# M500B.net
KiCad netlist of a schematic drawn in EAGLE
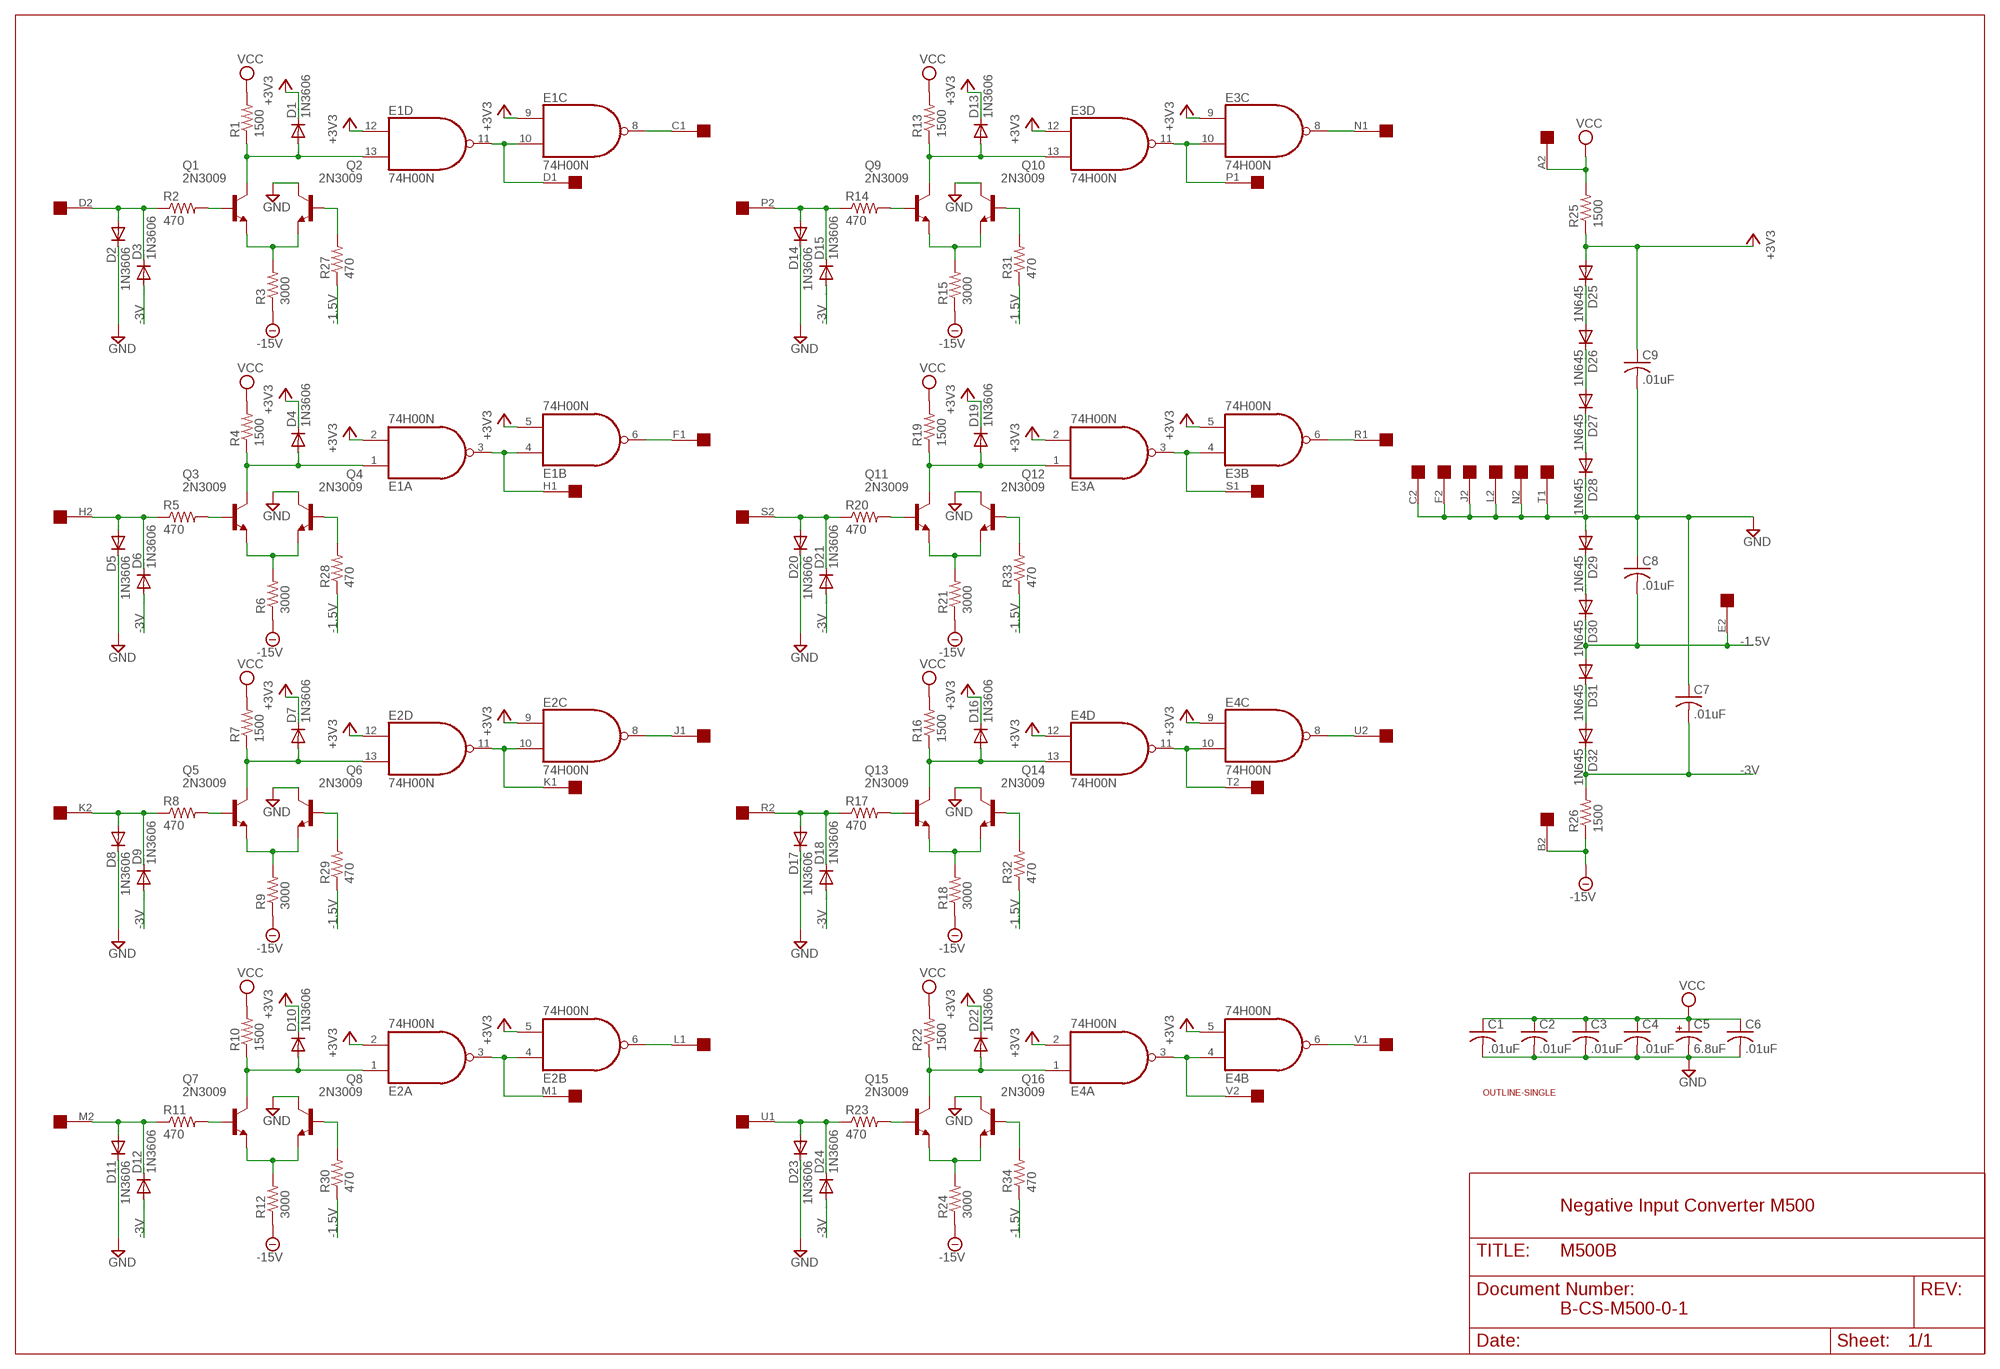
[diagram p0: schematic, sheet 1]

(export (version "E")
  (design (tool "Eeschema 10.0.6"))
  (components
    (comp (ref "C1")
      (value ".01uF")
      (footprint "eagle-import:C050-025X075")
      (libsource (lib "eagle-import") (part "C-US050-025X075"))
    )
    (comp (ref "C2")
      (value ".01uF")
      (footprint "eagle-import:C050-025X075")
      (libsource (lib "eagle-import") (part "C-US050-025X075"))
    )
    (comp (ref "C3")
      (value ".01uF")
      (footprint "eagle-import:C050-025X075")
      (libsource (lib "eagle-import") (part "C-US050-025X075"))
    )
    (comp (ref "C4")
      (value ".01uF")
      (footprint "eagle-import:C050-025X075")
      (libsource (lib "eagle-import") (part "C-US050-025X075"))
    )
    (comp (ref "C5")
      (value "6.8uF")
      (footprint "eagle-import:E12-8")
      (libsource (lib "eagle-import") (part "CPOL-USE20-8AXIAL"))
    )
    (comp (ref "C6")
      (value ".01uF")
      (footprint "eagle-import:C050-025X075")
      (libsource (lib "eagle-import") (part "C-US050-025X075"))
    )
    (comp (ref "C7")
      (value ".01uF")
      (footprint "eagle-import:C050-025X075")
      (libsource (lib "eagle-import") (part "C-US050-025X075"))
    )
    (comp (ref "C8")
      (value ".01uF")
      (footprint "eagle-import:C050-025X075")
      (libsource (lib "eagle-import") (part "C-US050-025X075"))
    )
    (comp (ref "C9")
      (value ".01uF")
      (footprint "eagle-import:C050-025X075")
      (libsource (lib "eagle-import") (part "C-US050-025X075"))
    )
    (comp (ref "D1")
      (value "1N3606")
      (footprint "eagle-import:DO35-10")
      (libsource (lib "eagle-import") (part "1N4148DO35-10"))
    )
    (comp (ref "D2")
      (value "1N3606")
      (footprint "eagle-import:DO35-10")
      (libsource (lib "eagle-import") (part "1N4148DO35-10"))
    )
    (comp (ref "D3")
      (value "1N3606")
      (footprint "eagle-import:DO35-10")
      (libsource (lib "eagle-import") (part "1N4148DO35-10"))
    )
    (comp (ref "D4")
      (value "1N3606")
      (footprint "eagle-import:DO35-10")
      (libsource (lib "eagle-import") (part "1N4148DO35-10"))
    )
    (comp (ref "D5")
      (value "1N3606")
      (footprint "eagle-import:DO35-10")
      (libsource (lib "eagle-import") (part "1N4148DO35-10"))
    )
    (comp (ref "D6")
      (value "1N3606")
      (footprint "eagle-import:DO35-10")
      (libsource (lib "eagle-import") (part "1N4148DO35-10"))
    )
    (comp (ref "D7")
      (value "1N3606")
      (footprint "eagle-import:DO35-10")
      (libsource (lib "eagle-import") (part "1N4148DO35-10"))
    )
    (comp (ref "D8")
      (value "1N3606")
      (footprint "eagle-import:DO35-10")
      (libsource (lib "eagle-import") (part "1N4148DO35-10"))
    )
    (comp (ref "D9")
      (value "1N3606")
      (footprint "eagle-import:DO35-10")
      (libsource (lib "eagle-import") (part "1N4148DO35-10"))
    )
    (comp (ref "D10")
      (value "1N3606")
      (footprint "eagle-import:DO35-10")
      (libsource (lib "eagle-import") (part "1N4148DO35-10"))
    )
    (comp (ref "D11")
      (value "1N3606")
      (footprint "eagle-import:DO35-10")
      (libsource (lib "eagle-import") (part "1N4148DO35-10"))
    )
    (comp (ref "D12")
      (value "1N3606")
      (footprint "eagle-import:DO35-10")
      (libsource (lib "eagle-import") (part "1N4148DO35-10"))
    )
    (comp (ref "D13")
      (value "1N3606")
      (footprint "eagle-import:DO35-10")
      (libsource (lib "eagle-import") (part "1N4148DO35-10"))
    )
    (comp (ref "D14")
      (value "1N3606")
      (footprint "eagle-import:DO35-10")
      (libsource (lib "eagle-import") (part "1N4148DO35-10"))
    )
    (comp (ref "D15")
      (value "1N3606")
      (footprint "eagle-import:DO35-10")
      (libsource (lib "eagle-import") (part "1N4148DO35-10"))
    )
    (comp (ref "D16")
      (value "1N3606")
      (footprint "eagle-import:DO35-10")
      (libsource (lib "eagle-import") (part "1N4148DO35-10"))
    )
    (comp (ref "D17")
      (value "1N3606")
      (footprint "eagle-import:DO35-10")
      (libsource (lib "eagle-import") (part "1N4148DO35-10"))
    )
    (comp (ref "D18")
      (value "1N3606")
      (footprint "eagle-import:DO35-10")
      (libsource (lib "eagle-import") (part "1N4148DO35-10"))
    )
    (comp (ref "D19")
      (value "1N3606")
      (footprint "eagle-import:DO35-10")
      (libsource (lib "eagle-import") (part "1N4148DO35-10"))
    )
    (comp (ref "D20")
      (value "1N3606")
      (footprint "eagle-import:DO35-10")
      (libsource (lib "eagle-import") (part "1N4148DO35-10"))
    )
    (comp (ref "D21")
      (value "1N3606")
      (footprint "eagle-import:DO35-10")
      (libsource (lib "eagle-import") (part "1N4148DO35-10"))
    )
    (comp (ref "D22")
      (value "1N3606")
      (footprint "eagle-import:DO35-10")
      (libsource (lib "eagle-import") (part "1N4148DO35-10"))
    )
    (comp (ref "D23")
      (value "1N3606")
      (footprint "eagle-import:DO35-10")
      (libsource (lib "eagle-import") (part "1N4148DO35-10"))
    )
    (comp (ref "D24")
      (value "1N3606")
      (footprint "eagle-import:DO35-10")
      (libsource (lib "eagle-import") (part "1N4148DO35-10"))
    )
    (comp (ref "D25")
      (value "1N645")
      (footprint "eagle-import:DO35-10")
      (libsource (lib "eagle-import") (part "1N4148DO35-10"))
    )
    (comp (ref "D26")
      (value "1N645")
      (footprint "eagle-import:DO35-10")
      (libsource (lib "eagle-import") (part "1N4148DO35-10"))
    )
    (comp (ref "D27")
      (value "1N645")
      (footprint "eagle-import:DO35-10")
      (libsource (lib "eagle-import") (part "1N4148DO35-10"))
    )
    (comp (ref "D28")
      (value "1N645")
      (footprint "eagle-import:DO35-10")
      (libsource (lib "eagle-import") (part "1N4148DO35-10"))
    )
    (comp (ref "D29")
      (value "1N645")
      (footprint "eagle-import:DO35-10")
      (libsource (lib "eagle-import") (part "1N4148DO35-10"))
    )
    (comp (ref "D30")
      (value "1N645")
      (footprint "eagle-import:DO35-10")
      (libsource (lib "eagle-import") (part "1N4148DO35-10"))
    )
    (comp (ref "D31")
      (value "1N645")
      (footprint "eagle-import:DO35-10")
      (libsource (lib "eagle-import") (part "1N4148DO35-10"))
    )
    (comp (ref "D32")
      (value "1N645")
      (footprint "eagle-import:DO35-10")
      (libsource (lib "eagle-import") (part "1N4148DO35-10"))
    )
    (comp (ref "E1")
      (value "74H00N")
      (footprint "eagle-import:DIL14")
      (libsource (lib "eagle-import") (part "7400N"))
    )
    (comp (ref "E2")
      (value "74H00N")
      (footprint "eagle-import:DIL14")
      (libsource (lib "eagle-import") (part "7400N"))
    )
    (comp (ref "E3")
      (value "74H00N")
      (footprint "eagle-import:DIL14")
      (libsource (lib "eagle-import") (part "7400N"))
    )
    (comp (ref "E4")
      (value "74H00N")
      (footprint "eagle-import:DIL14")
      (libsource (lib "eagle-import") (part "7400N"))
    )
    (comp (ref "Q1")
      (value "2N3009")
      (footprint "eagle-import:TO39")
      (libsource (lib "eagle-import") (part "2N3019"))
    )
    (comp (ref "Q2")
      (value "2N3009")
      (footprint "eagle-import:TO39")
      (libsource (lib "eagle-import") (part "2N3019"))
    )
    (comp (ref "Q3")
      (value "2N3009")
      (footprint "eagle-import:TO39")
      (libsource (lib "eagle-import") (part "2N3019"))
    )
    (comp (ref "Q4")
      (value "2N3009")
      (footprint "eagle-import:TO39")
      (libsource (lib "eagle-import") (part "2N3019"))
    )
    (comp (ref "Q5")
      (value "2N3009")
      (footprint "eagle-import:TO39")
      (libsource (lib "eagle-import") (part "2N3019"))
    )
    (comp (ref "Q6")
      (value "2N3009")
      (footprint "eagle-import:TO39")
      (libsource (lib "eagle-import") (part "2N3019"))
    )
    (comp (ref "Q7")
      (value "2N3009")
      (footprint "eagle-import:TO39")
      (libsource (lib "eagle-import") (part "2N3019"))
    )
    (comp (ref "Q8")
      (value "2N3009")
      (footprint "eagle-import:TO39")
      (libsource (lib "eagle-import") (part "2N3019"))
    )
    (comp (ref "Q9")
      (value "2N3009")
      (footprint "eagle-import:TO39")
      (libsource (lib "eagle-import") (part "2N3019"))
    )
    (comp (ref "Q10")
      (value "2N3009")
      (footprint "eagle-import:TO39")
      (libsource (lib "eagle-import") (part "2N3019"))
    )
    (comp (ref "Q11")
      (value "2N3009")
      (footprint "eagle-import:TO39")
      (libsource (lib "eagle-import") (part "2N3019"))
    )
    (comp (ref "Q12")
      (value "2N3009")
      (footprint "eagle-import:TO39")
      (libsource (lib "eagle-import") (part "2N3019"))
    )
    (comp (ref "Q13")
      (value "2N3009")
      (footprint "eagle-import:TO39")
      (libsource (lib "eagle-import") (part "2N3019"))
    )
    (comp (ref "Q14")
      (value "2N3009")
      (footprint "eagle-import:TO39")
      (libsource (lib "eagle-import") (part "2N3019"))
    )
    (comp (ref "Q15")
      (value "2N3009")
      (footprint "eagle-import:TO39")
      (libsource (lib "eagle-import") (part "2N3019"))
    )
    (comp (ref "Q16")
      (value "2N3009")
      (footprint "eagle-import:TO39")
      (libsource (lib "eagle-import") (part "2N3019"))
    )
    (comp (ref "R1")
      (value "1500")
      (footprint "eagle-import:0207_10")
      (libsource (lib "eagle-import") (part "R-US_0207/10"))
    )
    (comp (ref "R2")
      (value "470")
      (footprint "eagle-import:0207_10")
      (libsource (lib "eagle-import") (part "R-US_0207/10"))
    )
    (comp (ref "R3")
      (value "3000")
      (footprint "eagle-import:0207_10")
      (libsource (lib "eagle-import") (part "R-US_0207/10"))
    )
    (comp (ref "R4")
      (value "1500")
      (footprint "eagle-import:0207_10")
      (libsource (lib "eagle-import") (part "R-US_0207/10"))
    )
    (comp (ref "R5")
      (value "470")
      (footprint "eagle-import:0207_10")
      (libsource (lib "eagle-import") (part "R-US_0207/10"))
    )
    (comp (ref "R6")
      (value "3000")
      (footprint "eagle-import:0207_10")
      (libsource (lib "eagle-import") (part "R-US_0207/10"))
    )
    (comp (ref "R7")
      (value "1500")
      (footprint "eagle-import:0207_10")
      (libsource (lib "eagle-import") (part "R-US_0207/10"))
    )
    (comp (ref "R8")
      (value "470")
      (footprint "eagle-import:0207_10")
      (libsource (lib "eagle-import") (part "R-US_0207/10"))
    )
    (comp (ref "R9")
      (value "3000")
      (footprint "eagle-import:0207_10")
      (libsource (lib "eagle-import") (part "R-US_0207/10"))
    )
    (comp (ref "R10")
      (value "1500")
      (footprint "eagle-import:0207_10")
      (libsource (lib "eagle-import") (part "R-US_0207/10"))
    )
    (comp (ref "R11")
      (value "470")
      (footprint "eagle-import:0207_10")
      (libsource (lib "eagle-import") (part "R-US_0207/10"))
    )
    (comp (ref "R12")
      (value "3000")
      (footprint "eagle-import:0207_10")
      (libsource (lib "eagle-import") (part "R-US_0207/10"))
    )
    (comp (ref "R13")
      (value "1500")
      (footprint "eagle-import:0207_10")
      (libsource (lib "eagle-import") (part "R-US_0207/10"))
    )
    (comp (ref "R14")
      (value "470")
      (footprint "eagle-import:0207_10")
      (libsource (lib "eagle-import") (part "R-US_0207/10"))
    )
    (comp (ref "R15")
      (value "3000")
      (footprint "eagle-import:0207_10")
      (libsource (lib "eagle-import") (part "R-US_0207/10"))
    )
    (comp (ref "R16")
      (value "1500")
      (footprint "eagle-import:0207_10")
      (libsource (lib "eagle-import") (part "R-US_0207/10"))
    )
    (comp (ref "R17")
      (value "470")
      (footprint "eagle-import:0207_10")
      (libsource (lib "eagle-import") (part "R-US_0207/10"))
    )
    (comp (ref "R18")
      (value "3000")
      (footprint "eagle-import:0207_10")
      (libsource (lib "eagle-import") (part "R-US_0207/10"))
    )
    (comp (ref "R19")
      (value "1500")
      (footprint "eagle-import:0207_10")
      (libsource (lib "eagle-import") (part "R-US_0207/10"))
    )
    (comp (ref "R20")
      (value "470")
      (footprint "eagle-import:0207_10")
      (libsource (lib "eagle-import") (part "R-US_0207/10"))
    )
    (comp (ref "R21")
      (value "3000")
      (footprint "eagle-import:0207_10")
      (libsource (lib "eagle-import") (part "R-US_0207/10"))
    )
    (comp (ref "R22")
      (value "1500")
      (footprint "eagle-import:0207_10")
      (libsource (lib "eagle-import") (part "R-US_0207/10"))
    )
    (comp (ref "R23")
      (value "470")
      (footprint "eagle-import:0207_10")
      (libsource (lib "eagle-import") (part "R-US_0207/10"))
    )
    (comp (ref "R24")
      (value "3000")
      (footprint "eagle-import:0207_10")
      (libsource (lib "eagle-import") (part "R-US_0207/10"))
    )
    (comp (ref "R25")
      (value "1500")
      (footprint "eagle-import:0207_10")
      (libsource (lib "eagle-import") (part "R-US_0207/10"))
    )
    (comp (ref "R26")
      (value "1500")
      (footprint "eagle-import:0207_10")
      (libsource (lib "eagle-import") (part "R-US_0207/10"))
    )
    (comp (ref "R27")
      (value "470")
      (footprint "eagle-import:0207_10")
      (libsource (lib "eagle-import") (part "R-US_0207/10"))
    )
    (comp (ref "R28")
      (value "470")
      (footprint "eagle-import:0207_10")
      (libsource (lib "eagle-import") (part "R-US_0207/10"))
    )
    (comp (ref "R29")
      (value "470")
      (footprint "eagle-import:0207_10")
      (libsource (lib "eagle-import") (part "R-US_0207/10"))
    )
    (comp (ref "R30")
      (value "470")
      (footprint "eagle-import:0207_10")
      (libsource (lib "eagle-import") (part "R-US_0207/10"))
    )
    (comp (ref "R31")
      (value "470")
      (footprint "eagle-import:0207_10")
      (libsource (lib "eagle-import") (part "R-US_0207/10"))
    )
    (comp (ref "R32")
      (value "470")
      (footprint "eagle-import:0207_10")
      (libsource (lib "eagle-import") (part "R-US_0207/10"))
    )
    (comp (ref "R33")
      (value "470")
      (footprint "eagle-import:0207_10")
      (libsource (lib "eagle-import") (part "R-US_0207/10"))
    )
    (comp (ref "R34")
      (value "470")
      (footprint "eagle-import:0207_10")
      (libsource (lib "eagle-import") (part "R-US_0207/10"))
    )
    (comp (ref "U$1")
      (value "OUTLINE-SINGLE")
      (footprint "eagle-import:SINGLE")
      (libsource (lib "eagle-import") (part "OUTLINE-SINGLE"))
    )
    (comp (ref "U$3")
      (value "SINGLE")
      (footprint "eagle-import:EDGE-CON2")
      (libsource (lib "eagle-import") (part "SINGLE"))
    )
  )
  (nets
    (net (code "1") (name "+3V3") (class "Default")
      (node (ref "C9") (pin "1") (pinfunction "1_1") (pintype "passive"))
      (node (ref "D1") (pin "C") (pinfunction "C_C") (pintype "passive"))
      (node (ref "D10") (pin "C") (pinfunction "C_C") (pintype "passive"))
      (node (ref "D13") (pin "C") (pinfunction "C_C") (pintype "passive"))
      (node (ref "D16") (pin "C") (pinfunction "C_C") (pintype "passive"))
      (node (ref "D19") (pin "C") (pinfunction "C_C") (pintype "passive"))
      (node (ref "D22") (pin "C") (pinfunction "C_C") (pintype "passive"))
      (node (ref "D25") (pin "A") (pinfunction "A_A") (pintype "passive"))
      (node (ref "D4") (pin "C") (pinfunction "C_C") (pintype "passive"))
      (node (ref "D7") (pin "C") (pinfunction "C_C") (pintype "passive"))
      (node (ref "E1") (pin "12") (pinfunction "I0_12") (pintype "input"))
      (node (ref "E1") (pin "2") (pinfunction "I1_2") (pintype "input"))
      (node (ref "E1") (pin "5") (pinfunction "I1_5") (pintype "input"))
      (node (ref "E1") (pin "9") (pinfunction "I0_9") (pintype "input"))
      (node (ref "E2") (pin "12") (pinfunction "I0_12") (pintype "input"))
      (node (ref "E2") (pin "2") (pinfunction "I1_2") (pintype "input"))
      (node (ref "E2") (pin "5") (pinfunction "I1_5") (pintype "input"))
      (node (ref "E2") (pin "9") (pinfunction "I0_9") (pintype "input"))
      (node (ref "E3") (pin "12") (pinfunction "I0_12") (pintype "input"))
      (node (ref "E3") (pin "2") (pinfunction "I1_2") (pintype "input"))
      (node (ref "E3") (pin "5") (pinfunction "I1_5") (pintype "input"))
      (node (ref "E3") (pin "9") (pinfunction "I0_9") (pintype "input"))
      (node (ref "E4") (pin "12") (pinfunction "I0_12") (pintype "input"))
      (node (ref "E4") (pin "2") (pinfunction "I1_2") (pintype "input"))
      (node (ref "E4") (pin "5") (pinfunction "I1_5") (pintype "input"))
      (node (ref "E4") (pin "9") (pinfunction "I0_9") (pintype "input"))
      (node (ref "R25") (pin "1") (pinfunction "1_1") (pintype "passive"))
    )
    (net (code "2") (name "-15V") (class "Default")
      (node (ref "R12") (pin "1") (pinfunction "1_1") (pintype "passive"))
      (node (ref "R15") (pin "1") (pinfunction "1_1") (pintype "passive"))
      (node (ref "R18") (pin "1") (pinfunction "1_1") (pintype "passive"))
      (node (ref "R21") (pin "1") (pinfunction "1_1") (pintype "passive"))
      (node (ref "R24") (pin "1") (pinfunction "1_1") (pintype "passive"))
      (node (ref "R26") (pin "1") (pinfunction "1_1") (pintype "passive"))
      (node (ref "R3") (pin "1") (pinfunction "1_1") (pintype "passive"))
      (node (ref "R6") (pin "1") (pinfunction "1_1") (pintype "passive"))
      (node (ref "R9") (pin "1") (pinfunction "1_1") (pintype "passive"))
      (node (ref "U$3") (pin "B2") (pinfunction "1_B2") (pintype "bidirectional"))
    )
    (net (code "3") (name "/-1.5V") (class "Default")
      (node (ref "C8") (pin "2") (pinfunction "2_2") (pintype "passive"))
      (node (ref "D30") (pin "C") (pinfunction "C_C") (pintype "passive"))
      (node (ref "D31") (pin "A") (pinfunction "A_A") (pintype "passive"))
      (node (ref "R27") (pin "1") (pinfunction "1_1") (pintype "passive"))
      (node (ref "R28") (pin "1") (pinfunction "1_1") (pintype "passive"))
      (node (ref "R29") (pin "1") (pinfunction "1_1") (pintype "passive"))
      (node (ref "R30") (pin "1") (pinfunction "1_1") (pintype "passive"))
      (node (ref "R31") (pin "1") (pinfunction "1_1") (pintype "passive"))
      (node (ref "R32") (pin "1") (pinfunction "1_1") (pintype "passive"))
      (node (ref "R33") (pin "1") (pinfunction "1_1") (pintype "passive"))
      (node (ref "R34") (pin "1") (pinfunction "1_1") (pintype "passive"))
      (node (ref "U$3") (pin "E2") (pinfunction "1_E2") (pintype "bidirectional"))
    )
    (net (code "4") (name "/-3V") (class "Default")
      (node (ref "C7") (pin "2") (pinfunction "2_2") (pintype "passive"))
      (node (ref "D12") (pin "A") (pinfunction "A_A") (pintype "passive"))
      (node (ref "D15") (pin "A") (pinfunction "A_A") (pintype "passive"))
      (node (ref "D18") (pin "A") (pinfunction "A_A") (pintype "passive"))
      (node (ref "D21") (pin "A") (pinfunction "A_A") (pintype "passive"))
      (node (ref "D24") (pin "A") (pinfunction "A_A") (pintype "passive"))
      (node (ref "D3") (pin "A") (pinfunction "A_A") (pintype "passive"))
      (node (ref "D32") (pin "C") (pinfunction "C_C") (pintype "passive"))
      (node (ref "D6") (pin "A") (pinfunction "A_A") (pintype "passive"))
      (node (ref "D9") (pin "A") (pinfunction "A_A") (pintype "passive"))
      (node (ref "R26") (pin "2") (pinfunction "2_2") (pintype "passive"))
    )
    (net (code "5") (name "GND") (class "Default")
      (node (ref "C1") (pin "2") (pinfunction "2_2") (pintype "passive"))
      (node (ref "C2") (pin "2") (pinfunction "2_2") (pintype "passive"))
      (node (ref "C3") (pin "2") (pinfunction "2_2") (pintype "passive"))
      (node (ref "C4") (pin "2") (pinfunction "2_2") (pintype "passive"))
      (node (ref "C5") (pin "-") (pinfunction "-_-") (pintype "passive"))
      (node (ref "C6") (pin "2") (pinfunction "2_2") (pintype "passive"))
      (node (ref "C7") (pin "1") (pinfunction "1_1") (pintype "passive"))
      (node (ref "C8") (pin "1") (pinfunction "1_1") (pintype "passive"))
      (node (ref "C9") (pin "2") (pinfunction "2_2") (pintype "passive"))
      (node (ref "D11") (pin "C") (pinfunction "C_C") (pintype "passive"))
      (node (ref "D14") (pin "C") (pinfunction "C_C") (pintype "passive"))
      (node (ref "D17") (pin "C") (pinfunction "C_C") (pintype "passive"))
      (node (ref "D2") (pin "C") (pinfunction "C_C") (pintype "passive"))
      (node (ref "D20") (pin "C") (pinfunction "C_C") (pintype "passive"))
      (node (ref "D23") (pin "C") (pinfunction "C_C") (pintype "passive"))
      (node (ref "D28") (pin "C") (pinfunction "C_C") (pintype "passive"))
      (node (ref "D29") (pin "A") (pinfunction "A_A") (pintype "passive"))
      (node (ref "D5") (pin "C") (pinfunction "C_C") (pintype "passive"))
      (node (ref "D8") (pin "C") (pinfunction "C_C") (pintype "passive"))
      (node (ref "Q10") (pin "3") (pinfunction "C_3") (pintype "passive"))
      (node (ref "Q12") (pin "3") (pinfunction "C_3") (pintype "passive"))
      (node (ref "Q14") (pin "3") (pinfunction "C_3") (pintype "passive"))
      (node (ref "Q16") (pin "3") (pinfunction "C_3") (pintype "passive"))
      (node (ref "Q2") (pin "3") (pinfunction "C_3") (pintype "passive"))
      (node (ref "Q4") (pin "3") (pinfunction "C_3") (pintype "passive"))
      (node (ref "Q6") (pin "3") (pinfunction "C_3") (pintype "passive"))
      (node (ref "Q8") (pin "3") (pinfunction "C_3") (pintype "passive"))
      (node (ref "U$3") (pin "C2") (pinfunction "1_C2") (pintype "bidirectional"))
      (node (ref "U$3") (pin "F2") (pinfunction "1_F2") (pintype "bidirectional"))
      (node (ref "U$3") (pin "J2") (pinfunction "1_J2") (pintype "bidirectional"))
      (node (ref "U$3") (pin "L2") (pinfunction "1_L2") (pintype "bidirectional"))
      (node (ref "U$3") (pin "N2") (pinfunction "1_N2") (pintype "bidirectional"))
      (node (ref "U$3") (pin "T1") (pinfunction "1_T1") (pintype "bidirectional"))
    )
    (net (code "6") (name "Net-(D25-PadC)") (class "Default")
      (node (ref "D25") (pin "C") (pinfunction "C_C") (pintype "passive"))
      (node (ref "D26") (pin "A") (pinfunction "A_A") (pintype "passive"))
    )
    (net (code "7") (name "Net-(D26-PadC)") (class "Default")
      (node (ref "D26") (pin "C") (pinfunction "C_C") (pintype "passive"))
      (node (ref "D27") (pin "A") (pinfunction "A_A") (pintype "passive"))
    )
    (net (code "8") (name "Net-(D27-PadC)") (class "Default")
      (node (ref "D27") (pin "C") (pinfunction "C_C") (pintype "passive"))
      (node (ref "D28") (pin "A") (pinfunction "A_A") (pintype "passive"))
    )
    (net (code "9") (name "Net-(D29-PadC)") (class "Default")
      (node (ref "D29") (pin "C") (pinfunction "C_C") (pintype "passive"))
      (node (ref "D30") (pin "A") (pinfunction "A_A") (pintype "passive"))
    )
    (net (code "10") (name "Net-(D31-PadC)") (class "Default")
      (node (ref "D31") (pin "C") (pinfunction "C_C") (pintype "passive"))
      (node (ref "D32") (pin "A") (pinfunction "A_A") (pintype "passive"))
    )
    (net (code "11") (name "Net-(E1A-I0)") (class "Default")
      (node (ref "D4") (pin "A") (pinfunction "A_A") (pintype "passive"))
      (node (ref "E1") (pin "1") (pinfunction "I0_1") (pintype "input"))
      (node (ref "Q3") (pin "3") (pinfunction "C_3") (pintype "passive"))
      (node (ref "R4") (pin "1") (pinfunction "1_1") (pintype "passive"))
    )
    (net (code "12") (name "Net-(E1A-O)") (class "Default")
      (node (ref "E1") (pin "3") (pinfunction "O_3") (pintype "output"))
      (node (ref "E1") (pin "4") (pinfunction "I0_4") (pintype "input"))
      (node (ref "U$3") (pin "H1") (pinfunction "1_H1") (pintype "bidirectional"))
    )
    (net (code "13") (name "Net-(E1B-O)") (class "Default")
      (node (ref "E1") (pin "6") (pinfunction "O_6") (pintype "output"))
      (node (ref "U$3") (pin "F1") (pinfunction "1_F1") (pintype "bidirectional"))
    )
    (net (code "14") (name "Net-(E1C-I1)") (class "Default")
      (node (ref "E1") (pin "10") (pinfunction "I1_10") (pintype "input"))
      (node (ref "E1") (pin "11") (pinfunction "O_11") (pintype "output"))
      (node (ref "U$3") (pin "D1") (pinfunction "1_D1") (pintype "bidirectional"))
    )
    (net (code "15") (name "Net-(E1C-O)") (class "Default")
      (node (ref "E1") (pin "8") (pinfunction "O_8") (pintype "output"))
      (node (ref "U$3") (pin "C1") (pinfunction "1_C1") (pintype "bidirectional"))
    )
    (net (code "16") (name "Net-(E1D-I1)") (class "Default")
      (node (ref "D1") (pin "A") (pinfunction "A_A") (pintype "passive"))
      (node (ref "E1") (pin "13") (pinfunction "I1_13") (pintype "input"))
      (node (ref "Q1") (pin "3") (pinfunction "C_3") (pintype "passive"))
      (node (ref "R1") (pin "1") (pinfunction "1_1") (pintype "passive"))
    )
    (net (code "17") (name "Net-(E2A-I0)") (class "Default")
      (node (ref "D10") (pin "A") (pinfunction "A_A") (pintype "passive"))
      (node (ref "E2") (pin "1") (pinfunction "I0_1") (pintype "input"))
      (node (ref "Q7") (pin "3") (pinfunction "C_3") (pintype "passive"))
      (node (ref "R10") (pin "1") (pinfunction "1_1") (pintype "passive"))
    )
    (net (code "18") (name "Net-(E2A-O)") (class "Default")
      (node (ref "E2") (pin "3") (pinfunction "O_3") (pintype "output"))
      (node (ref "E2") (pin "4") (pinfunction "I0_4") (pintype "input"))
      (node (ref "U$3") (pin "M1") (pinfunction "1_M1") (pintype "bidirectional"))
    )
    (net (code "19") (name "Net-(E2B-O)") (class "Default")
      (node (ref "E2") (pin "6") (pinfunction "O_6") (pintype "output"))
      (node (ref "U$3") (pin "L1") (pinfunction "1_L1") (pintype "bidirectional"))
    )
    (net (code "20") (name "Net-(E2C-I1)") (class "Default")
      (node (ref "E2") (pin "10") (pinfunction "I1_10") (pintype "input"))
      (node (ref "E2") (pin "11") (pinfunction "O_11") (pintype "output"))
      (node (ref "U$3") (pin "K1") (pinfunction "1_K1") (pintype "bidirectional"))
    )
    (net (code "21") (name "Net-(E2C-O)") (class "Default")
      (node (ref "E2") (pin "8") (pinfunction "O_8") (pintype "output"))
      (node (ref "U$3") (pin "J1") (pinfunction "1_J1") (pintype "bidirectional"))
    )
    (net (code "22") (name "Net-(E2D-I1)") (class "Default")
      (node (ref "D7") (pin "A") (pinfunction "A_A") (pintype "passive"))
      (node (ref "E2") (pin "13") (pinfunction "I1_13") (pintype "input"))
      (node (ref "Q5") (pin "3") (pinfunction "C_3") (pintype "passive"))
      (node (ref "R7") (pin "1") (pinfunction "1_1") (pintype "passive"))
    )
    (net (code "23") (name "Net-(E3A-I0)") (class "Default")
      (node (ref "D19") (pin "A") (pinfunction "A_A") (pintype "passive"))
      (node (ref "E3") (pin "1") (pinfunction "I0_1") (pintype "input"))
      (node (ref "Q11") (pin "3") (pinfunction "C_3") (pintype "passive"))
      (node (ref "R19") (pin "1") (pinfunction "1_1") (pintype "passive"))
    )
    (net (code "24") (name "Net-(E3A-O)") (class "Default")
      (node (ref "E3") (pin "3") (pinfunction "O_3") (pintype "output"))
      (node (ref "E3") (pin "4") (pinfunction "I0_4") (pintype "input"))
      (node (ref "U$3") (pin "S1") (pinfunction "1_S1") (pintype "bidirectional"))
    )
    (net (code "25") (name "Net-(E3B-O)") (class "Default")
      (node (ref "E3") (pin "6") (pinfunction "O_6") (pintype "output"))
      (node (ref "U$3") (pin "R1") (pinfunction "1_R1") (pintype "bidirectional"))
    )
    (net (code "26") (name "Net-(E3C-I1)") (class "Default")
      (node (ref "E3") (pin "10") (pinfunction "I1_10") (pintype "input"))
      (node (ref "E3") (pin "11") (pinfunction "O_11") (pintype "output"))
      (node (ref "U$3") (pin "P1") (pinfunction "1_P1") (pintype "bidirectional"))
    )
    (net (code "27") (name "Net-(E3C-O)") (class "Default")
      (node (ref "E3") (pin "8") (pinfunction "O_8") (pintype "output"))
      (node (ref "U$3") (pin "N1") (pinfunction "1_N1") (pintype "bidirectional"))
    )
    (net (code "28") (name "Net-(E3D-I1)") (class "Default")
      (node (ref "D13") (pin "A") (pinfunction "A_A") (pintype "passive"))
      (node (ref "E3") (pin "13") (pinfunction "I1_13") (pintype "input"))
      (node (ref "Q9") (pin "3") (pinfunction "C_3") (pintype "passive"))
      (node (ref "R13") (pin "1") (pinfunction "1_1") (pintype "passive"))
    )
    (net (code "29") (name "Net-(E4A-I0)") (class "Default")
      (node (ref "D22") (pin "A") (pinfunction "A_A") (pintype "passive"))
      (node (ref "E4") (pin "1") (pinfunction "I0_1") (pintype "input"))
      (node (ref "Q15") (pin "3") (pinfunction "C_3") (pintype "passive"))
      (node (ref "R22") (pin "1") (pinfunction "1_1") (pintype "passive"))
    )
    (net (code "30") (name "Net-(E4A-O)") (class "Default")
      (node (ref "E4") (pin "3") (pinfunction "O_3") (pintype "output"))
      (node (ref "E4") (pin "4") (pinfunction "I0_4") (pintype "input"))
      (node (ref "U$3") (pin "V2") (pinfunction "1_V2") (pintype "bidirectional"))
    )
    (net (code "31") (name "Net-(E4B-O)") (class "Default")
      (node (ref "E4") (pin "6") (pinfunction "O_6") (pintype "output"))
      (node (ref "U$3") (pin "V1") (pinfunction "1_V1") (pintype "bidirectional"))
    )
    (net (code "32") (name "Net-(E4C-I1)") (class "Default")
      (node (ref "E4") (pin "10") (pinfunction "I1_10") (pintype "input"))
      (node (ref "E4") (pin "11") (pinfunction "O_11") (pintype "output"))
      (node (ref "U$3") (pin "T2") (pinfunction "1_T2") (pintype "bidirectional"))
    )
    (net (code "33") (name "Net-(E4C-O)") (class "Default")
      (node (ref "E4") (pin "8") (pinfunction "O_8") (pintype "output"))
      (node (ref "U$3") (pin "U2") (pinfunction "1_U2") (pintype "bidirectional"))
    )
    (net (code "34") (name "Net-(E4D-I1)") (class "Default")
      (node (ref "D16") (pin "A") (pinfunction "A_A") (pintype "passive"))
      (node (ref "E4") (pin "13") (pinfunction "I1_13") (pintype "input"))
      (node (ref "Q13") (pin "3") (pinfunction "C_3") (pintype "passive"))
      (node (ref "R16") (pin "1") (pinfunction "1_1") (pintype "passive"))
    )
    (net (code "35") (name "Net-(Q1-B)") (class "Default")
      (node (ref "Q1") (pin "2") (pinfunction "B_2") (pintype "passive"))
      (node (ref "R2") (pin "2") (pinfunction "2_2") (pintype "passive"))
    )
    (net (code "36") (name "Net-(Q1-E)") (class "Default")
      (node (ref "Q1") (pin "1") (pinfunction "E_1") (pintype "passive"))
      (node (ref "Q2") (pin "1") (pinfunction "E_1") (pintype "passive"))
      (node (ref "R3") (pin "2") (pinfunction "2_2") (pintype "passive"))
    )
    (net (code "37") (name "Net-(Q2-B)") (class "Default")
      (node (ref "Q2") (pin "2") (pinfunction "B_2") (pintype "passive"))
      (node (ref "R27") (pin "2") (pinfunction "2_2") (pintype "passive"))
    )
    (net (code "38") (name "Net-(Q3-B)") (class "Default")
      (node (ref "Q3") (pin "2") (pinfunction "B_2") (pintype "passive"))
      (node (ref "R5") (pin "2") (pinfunction "2_2") (pintype "passive"))
    )
    (net (code "39") (name "Net-(Q3-E)") (class "Default")
      (node (ref "Q3") (pin "1") (pinfunction "E_1") (pintype "passive"))
      (node (ref "Q4") (pin "1") (pinfunction "E_1") (pintype "passive"))
      (node (ref "R6") (pin "2") (pinfunction "2_2") (pintype "passive"))
    )
    (net (code "40") (name "Net-(Q4-B)") (class "Default")
      (node (ref "Q4") (pin "2") (pinfunction "B_2") (pintype "passive"))
      (node (ref "R28") (pin "2") (pinfunction "2_2") (pintype "passive"))
    )
    (net (code "41") (name "Net-(Q5-B)") (class "Default")
      (node (ref "Q5") (pin "2") (pinfunction "B_2") (pintype "passive"))
      (node (ref "R8") (pin "2") (pinfunction "2_2") (pintype "passive"))
    )
    (net (code "42") (name "Net-(Q5-E)") (class "Default")
      (node (ref "Q5") (pin "1") (pinfunction "E_1") (pintype "passive"))
      (node (ref "Q6") (pin "1") (pinfunction "E_1") (pintype "passive"))
      (node (ref "R9") (pin "2") (pinfunction "2_2") (pintype "passive"))
    )
    (net (code "43") (name "Net-(Q6-B)") (class "Default")
      (node (ref "Q6") (pin "2") (pinfunction "B_2") (pintype "passive"))
      (node (ref "R29") (pin "2") (pinfunction "2_2") (pintype "passive"))
    )
    (net (code "44") (name "Net-(Q7-B)") (class "Default")
      (node (ref "Q7") (pin "2") (pinfunction "B_2") (pintype "passive"))
      (node (ref "R11") (pin "2") (pinfunction "2_2") (pintype "passive"))
    )
    (net (code "45") (name "Net-(Q7-E)") (class "Default")
      (node (ref "Q7") (pin "1") (pinfunction "E_1") (pintype "passive"))
      (node (ref "Q8") (pin "1") (pinfunction "E_1") (pintype "passive"))
      (node (ref "R12") (pin "2") (pinfunction "2_2") (pintype "passive"))
    )
    (net (code "46") (name "Net-(Q8-B)") (class "Default")
      (node (ref "Q8") (pin "2") (pinfunction "B_2") (pintype "passive"))
      (node (ref "R30") (pin "2") (pinfunction "2_2") (pintype "passive"))
    )
    (net (code "47") (name "Net-(Q9-B)") (class "Default")
      (node (ref "Q9") (pin "2") (pinfunction "B_2") (pintype "passive"))
      (node (ref "R14") (pin "2") (pinfunction "2_2") (pintype "passive"))
    )
    (net (code "48") (name "Net-(Q10-B)") (class "Default")
      (node (ref "Q10") (pin "2") (pinfunction "B_2") (pintype "passive"))
      (node (ref "R31") (pin "2") (pinfunction "2_2") (pintype "passive"))
    )
    (net (code "49") (name "Net-(Q10-E)") (class "Default")
      (node (ref "Q10") (pin "1") (pinfunction "E_1") (pintype "passive"))
      (node (ref "Q9") (pin "1") (pinfunction "E_1") (pintype "passive"))
      (node (ref "R15") (pin "2") (pinfunction "2_2") (pintype "passive"))
    )
    (net (code "50") (name "Net-(Q11-B)") (class "Default")
      (node (ref "Q11") (pin "2") (pinfunction "B_2") (pintype "passive"))
      (node (ref "R20") (pin "2") (pinfunction "2_2") (pintype "passive"))
    )
    (net (code "51") (name "Net-(Q11-E)") (class "Default")
      (node (ref "Q11") (pin "1") (pinfunction "E_1") (pintype "passive"))
      (node (ref "Q12") (pin "1") (pinfunction "E_1") (pintype "passive"))
      (node (ref "R21") (pin "2") (pinfunction "2_2") (pintype "passive"))
    )
    (net (code "52") (name "Net-(Q12-B)") (class "Default")
      (node (ref "Q12") (pin "2") (pinfunction "B_2") (pintype "passive"))
      (node (ref "R33") (pin "2") (pinfunction "2_2") (pintype "passive"))
    )
    (net (code "53") (name "Net-(Q13-B)") (class "Default")
      (node (ref "Q13") (pin "2") (pinfunction "B_2") (pintype "passive"))
      (node (ref "R17") (pin "2") (pinfunction "2_2") (pintype "passive"))
    )
    (net (code "54") (name "Net-(Q13-E)") (class "Default")
      (node (ref "Q13") (pin "1") (pinfunction "E_1") (pintype "passive"))
      (node (ref "Q14") (pin "1") (pinfunction "E_1") (pintype "passive"))
      (node (ref "R18") (pin "2") (pinfunction "2_2") (pintype "passive"))
    )
    (net (code "55") (name "Net-(Q14-B)") (class "Default")
      (node (ref "Q14") (pin "2") (pinfunction "B_2") (pintype "passive"))
      (node (ref "R32") (pin "2") (pinfunction "2_2") (pintype "passive"))
    )
    (net (code "56") (name "Net-(Q15-B)") (class "Default")
      (node (ref "Q15") (pin "2") (pinfunction "B_2") (pintype "passive"))
      (node (ref "R23") (pin "2") (pinfunction "2_2") (pintype "passive"))
    )
    (net (code "57") (name "Net-(Q15-E)") (class "Default")
      (node (ref "Q15") (pin "1") (pinfunction "E_1") (pintype "passive"))
      (node (ref "Q16") (pin "1") (pinfunction "E_1") (pintype "passive"))
      (node (ref "R24") (pin "2") (pinfunction "2_2") (pintype "passive"))
    )
    (net (code "58") (name "Net-(Q16-B)") (class "Default")
      (node (ref "Q16") (pin "2") (pinfunction "B_2") (pintype "passive"))
      (node (ref "R34") (pin "2") (pinfunction "2_2") (pintype "passive"))
    )
    (net (code "59") (name "Net-(U$3AB-1)") (class "Default")
      (node (ref "D17") (pin "A") (pinfunction "A_A") (pintype "passive"))
      (node (ref "D18") (pin "C") (pinfunction "C_C") (pintype "passive"))
      (node (ref "R17") (pin "1") (pinfunction "1_1") (pintype "passive"))
      (node (ref "U$3") (pin "R2") (pinfunction "1_R2") (pintype "bidirectional"))
    )
    (net (code "60") (name "Net-(U$3AD-1)") (class "Default")
      (node (ref "D20") (pin "A") (pinfunction "A_A") (pintype "passive"))
      (node (ref "D21") (pin "C") (pinfunction "C_C") (pintype "passive"))
      (node (ref "R20") (pin "1") (pinfunction "1_1") (pintype "passive"))
      (node (ref "U$3") (pin "S2") (pinfunction "1_S2") (pintype "bidirectional"))
    )
    (net (code "61") (name "Net-(U$3AG-1)") (class "Default")
      (node (ref "D23") (pin "A") (pinfunction "A_A") (pintype "passive"))
      (node (ref "D24") (pin "C") (pinfunction "C_C") (pintype "passive"))
      (node (ref "R23") (pin "1") (pinfunction "1_1") (pintype "passive"))
      (node (ref "U$3") (pin "U1") (pinfunction "1_U1") (pintype "bidirectional"))
    )
    (net (code "62") (name "Net-(U$3H-1)") (class "Default")
      (node (ref "D2") (pin "A") (pinfunction "A_A") (pintype "passive"))
      (node (ref "D3") (pin "C") (pinfunction "C_C") (pintype "passive"))
      (node (ref "R2") (pin "1") (pinfunction "1_1") (pintype "passive"))
      (node (ref "U$3") (pin "D2") (pinfunction "1_D2") (pintype "bidirectional"))
    )
    (net (code "63") (name "Net-(U$3N-1)") (class "Default")
      (node (ref "D5") (pin "A") (pinfunction "A_A") (pintype "passive"))
      (node (ref "D6") (pin "C") (pinfunction "C_C") (pintype "passive"))
      (node (ref "R5") (pin "1") (pinfunction "1_1") (pintype "passive"))
      (node (ref "U$3") (pin "H2") (pinfunction "1_H2") (pintype "bidirectional"))
    )
    (net (code "64") (name "Net-(U$3R-1)") (class "Default")
      (node (ref "D8") (pin "A") (pinfunction "A_A") (pintype "passive"))
      (node (ref "D9") (pin "C") (pinfunction "C_C") (pintype "passive"))
      (node (ref "R8") (pin "1") (pinfunction "1_1") (pintype "passive"))
      (node (ref "U$3") (pin "K2") (pinfunction "1_K2") (pintype "bidirectional"))
    )
    (net (code "65") (name "Net-(U$3V-1)") (class "Default")
      (node (ref "D11") (pin "A") (pinfunction "A_A") (pintype "passive"))
      (node (ref "D12") (pin "C") (pinfunction "C_C") (pintype "passive"))
      (node (ref "R11") (pin "1") (pinfunction "1_1") (pintype "passive"))
      (node (ref "U$3") (pin "M2") (pinfunction "1_M2") (pintype "bidirectional"))
    )
    (net (code "66") (name "Net-(U$3Z-1)") (class "Default")
      (node (ref "D14") (pin "A") (pinfunction "A_A") (pintype "passive"))
      (node (ref "D15") (pin "C") (pinfunction "C_C") (pintype "passive"))
      (node (ref "R14") (pin "1") (pinfunction "1_1") (pintype "passive"))
      (node (ref "U$3") (pin "P2") (pinfunction "1_P2") (pintype "bidirectional"))
    )
    (net (code "67") (name "VCC") (class "Default")
      (node (ref "C1") (pin "1") (pinfunction "1_1") (pintype "passive"))
      (node (ref "C2") (pin "1") (pinfunction "1_1") (pintype "passive"))
      (node (ref "C3") (pin "1") (pinfunction "1_1") (pintype "passive"))
      (node (ref "C4") (pin "1") (pinfunction "1_1") (pintype "passive"))
      (node (ref "C5") (pin "+") (pinfunction "+_+") (pintype "passive"))
      (node (ref "C6") (pin "1") (pinfunction "1_1") (pintype "passive"))
      (node (ref "R1") (pin "2") (pinfunction "2_2") (pintype "passive"))
      (node (ref "R10") (pin "2") (pinfunction "2_2") (pintype "passive"))
      (node (ref "R13") (pin "2") (pinfunction "2_2") (pintype "passive"))
      (node (ref "R16") (pin "2") (pinfunction "2_2") (pintype "passive"))
      (node (ref "R19") (pin "2") (pinfunction "2_2") (pintype "passive"))
      (node (ref "R22") (pin "2") (pinfunction "2_2") (pintype "passive"))
      (node (ref "R25") (pin "2") (pinfunction "2_2") (pintype "passive"))
      (node (ref "R4") (pin "2") (pinfunction "2_2") (pintype "passive"))
      (node (ref "R7") (pin "2") (pinfunction "2_2") (pintype "passive"))
      (node (ref "U$3") (pin "A2") (pinfunction "1_A2") (pintype "bidirectional"))
    )
  )
)
